# table1.net
KiCad netlist of a schematic drawn in EasyEDA
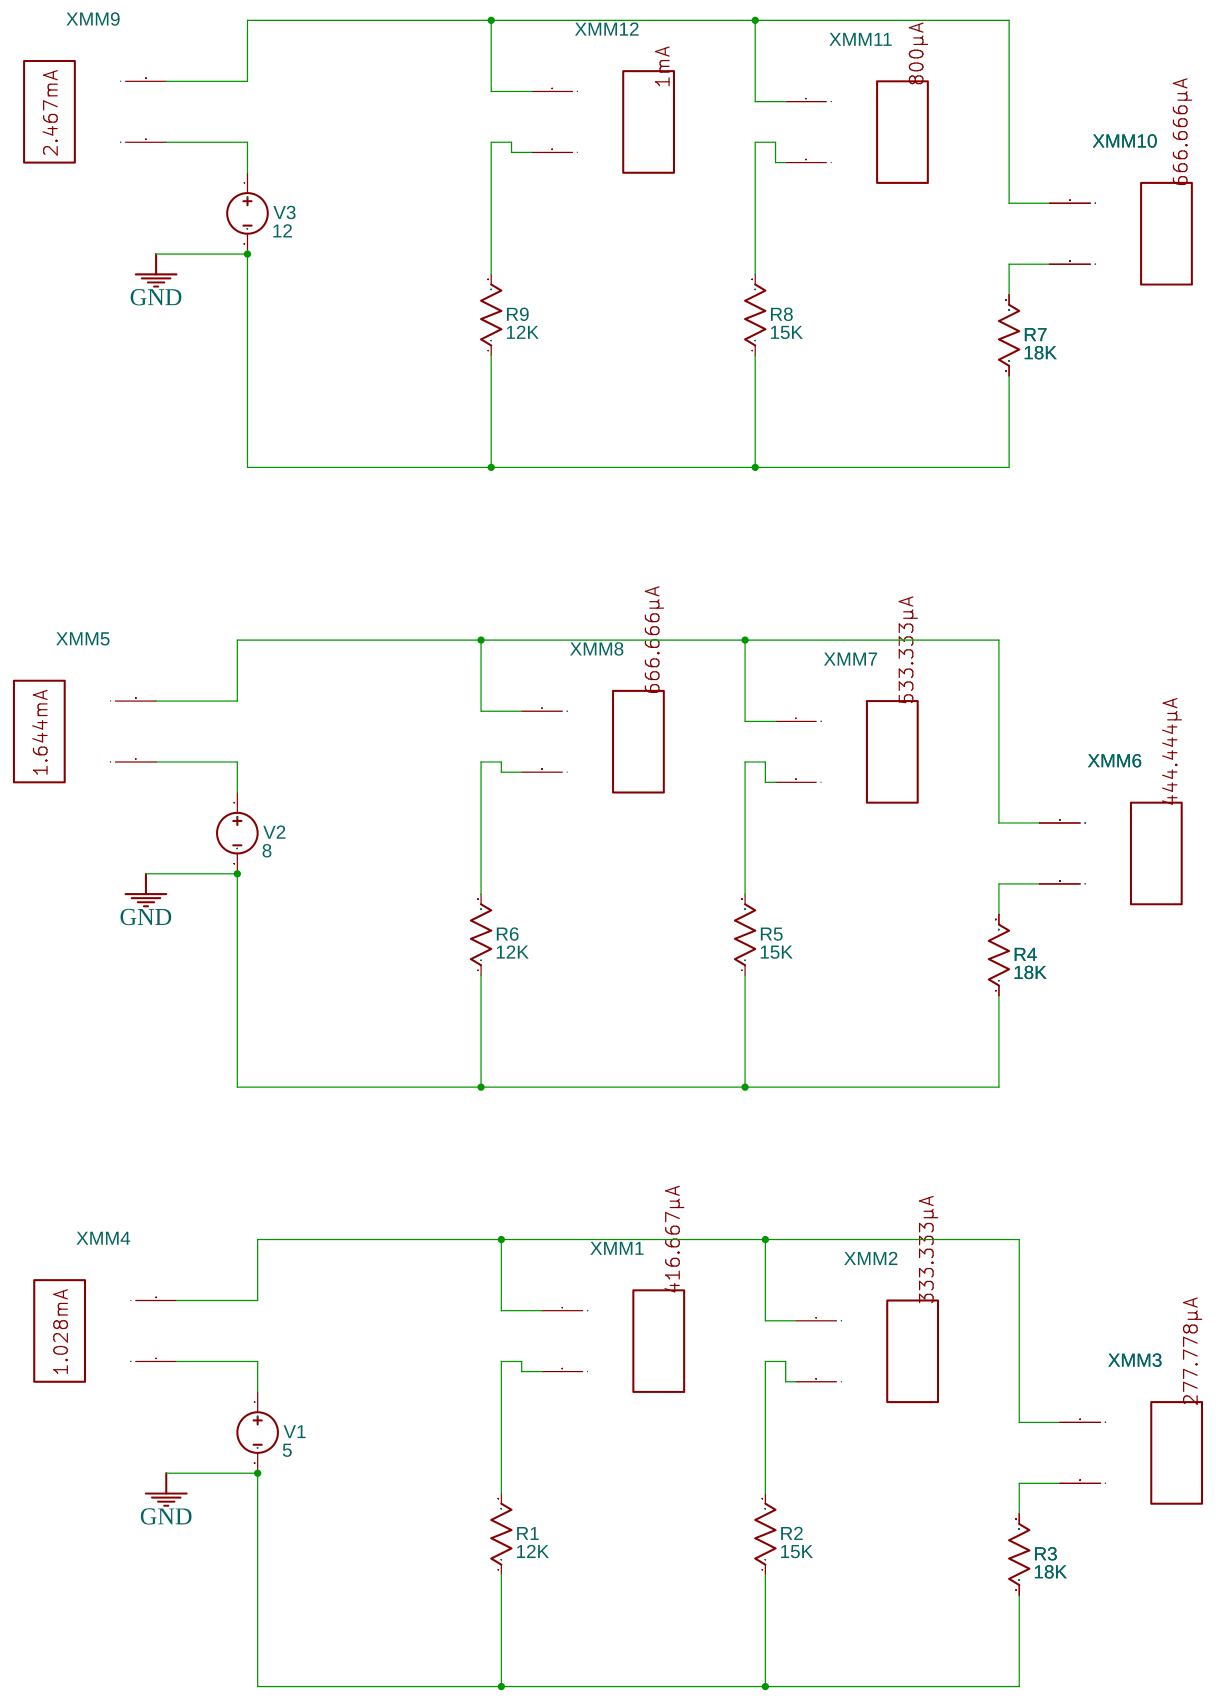
[diagram p0: schematic sheet]

(export (version "E")
  (design (tool "Eeschema 10.0.6"))
  (components
    (comp (ref "R1") (value "12K") (libsource (lib "") (part "Resistor_US")))
    (comp (ref "R2") (value "15K") (libsource (lib "") (part "Resistor_US")))
    (comp (ref "R3") (value "18K") (libsource (lib "") (part "Resistor_US")))
    (comp (ref "R4") (value "18K") (libsource (lib "") (part "Resistor_US")))
    (comp (ref "R5") (value "15K") (libsource (lib "") (part "Resistor_US")))
    (comp (ref "R6") (value "12K") (libsource (lib "") (part "Resistor_US")))
    (comp (ref "R7") (value "18K") (libsource (lib "") (part "Resistor_US")))
    (comp (ref "R8") (value "15K") (libsource (lib "") (part "Resistor_US")))
    (comp (ref "R9") (value "12K") (libsource (lib "") (part "Resistor_US")))
    (comp (ref "V1") (value "5") (libsource (lib "") (part "VDC")))
    (comp (ref "V2") (value "8") (libsource (lib "") (part "VDC")))
    (comp (ref "V3") (value "12") (libsource (lib "") (part "VDC")))
    (comp (ref "XMM1") (value "Multimeter") (libsource (lib "") (part "MULTIMETER_6")))
    (comp (ref "XMM2") (value "Multimeter") (libsource (lib "") (part "MULTIMETER_2")))
    (comp (ref "XMM3") (value "Multimeter") (libsource (lib "") (part "MULTIMETER_7")))
    (comp (ref "XMM4") (value "Multimeter") (libsource (lib "") (part "MULTIMETER_8")))
    (comp (ref "XMM5") (value "Multimeter") (libsource (lib "") (part "MULTIMETER_3")))
    (comp (ref "XMM6") (value "Multimeter") (libsource (lib "") (part "MULTIMETER_4")))
    (comp (ref "XMM7") (value "Multimeter") (libsource (lib "") (part "MULTIMETER_1")))
    (comp (ref "XMM8") (value "Multimeter") (libsource (lib "") (part "MULTIMETER")))
    (comp (ref "XMM9") (value "Multimeter") (libsource (lib "") (part "MULTIMETER_9")))
    (comp (ref "XMM10") (value "Multimeter") (libsource (lib "") (part "MULTIMETER")))
    (comp (ref "XMM11") (value "Multimeter") (libsource (lib "") (part "MULTIMETER_5")))
    (comp (ref "XMM12") (value "Multimeter") (libsource (lib "") (part "MULTIMETER_10")))
  )
  (nets
    (net (code "1") (name "GND") (class "Default")
      (node (ref "R1") (pin "1") (pinfunction "1_1") (pintype "unspecified"))
      (node (ref "R2") (pin "1") (pinfunction "1_1") (pintype "unspecified"))
      (node (ref "R3") (pin "1") (pinfunction "1_1") (pintype "unspecified"))
      (node (ref "R4") (pin "1") (pinfunction "1_1") (pintype "unspecified"))
      (node (ref "R5") (pin "1") (pinfunction "1_1") (pintype "unspecified"))
      (node (ref "R6") (pin "1") (pinfunction "1_1") (pintype "unspecified"))
      (node (ref "R7") (pin "1") (pinfunction "1_1") (pintype "unspecified"))
      (node (ref "R8") (pin "1") (pinfunction "1_1") (pintype "unspecified"))
      (node (ref "R9") (pin "1") (pinfunction "1_1") (pintype "unspecified"))
      (node (ref "V1") (pin "2") (pinfunction "2_2") (pintype "unspecified"))
      (node (ref "V2") (pin "2") (pinfunction "2_2") (pintype "unspecified"))
      (node (ref "V3") (pin "2") (pinfunction "2_2") (pintype "unspecified"))
    )
    (net (code "2") (name "Net-(XMM1-+)") (class "Default")
      (node (ref "XMM1") (pin "1") (pinfunction "+_1") (pintype "unspecified"))
      (node (ref "XMM2") (pin "1") (pinfunction "+_1") (pintype "unspecified"))
      (node (ref "XMM3") (pin "1") (pinfunction "+_1") (pintype "unspecified"))
      (node (ref "XMM4") (pin "2") (pinfunction "I_2") (pintype "unspecified"))
    )
    (net (code "3") (name "Net-(XMM1-I)") (class "Default")
      (node (ref "R1") (pin "2") (pinfunction "2_2") (pintype "unspecified"))
      (node (ref "XMM1") (pin "2") (pinfunction "I_2") (pintype "unspecified"))
    )
    (net (code "4") (name "Net-(XMM2-I)") (class "Default")
      (node (ref "R2") (pin "2") (pinfunction "2_2") (pintype "unspecified"))
      (node (ref "XMM2") (pin "2") (pinfunction "I_2") (pintype "unspecified"))
    )
    (net (code "5") (name "Net-(XMM3-I)") (class "Default")
      (node (ref "R3") (pin "2") (pinfunction "2_2") (pintype "unspecified"))
      (node (ref "XMM3") (pin "2") (pinfunction "I_2") (pintype "unspecified"))
    )
    (net (code "6") (name "Net-(XMM4-+)") (class "Default")
      (node (ref "V1") (pin "1") (pinfunction "1_1") (pintype "unspecified"))
      (node (ref "XMM4") (pin "1") (pinfunction "+_1") (pintype "unspecified"))
    )
    (net (code "7") (name "Net-(XMM5-+)") (class "Default")
      (node (ref "V2") (pin "1") (pinfunction "1_1") (pintype "unspecified"))
      (node (ref "XMM5") (pin "1") (pinfunction "+_1") (pintype "unspecified"))
    )
    (net (code "8") (name "Net-(XMM5-I)") (class "Default")
      (node (ref "XMM5") (pin "2") (pinfunction "I_2") (pintype "unspecified"))
      (node (ref "XMM6") (pin "1") (pinfunction "+_1") (pintype "unspecified"))
      (node (ref "XMM7") (pin "1") (pinfunction "+_1") (pintype "unspecified"))
      (node (ref "XMM8") (pin "1") (pinfunction "+_1") (pintype "unspecified"))
    )
    (net (code "9") (name "Net-(XMM6-I)") (class "Default")
      (node (ref "R4") (pin "2") (pinfunction "2_2") (pintype "unspecified"))
      (node (ref "XMM6") (pin "2") (pinfunction "I_2") (pintype "unspecified"))
    )
    (net (code "10") (name "Net-(XMM7-I)") (class "Default")
      (node (ref "R5") (pin "2") (pinfunction "2_2") (pintype "unspecified"))
      (node (ref "XMM7") (pin "2") (pinfunction "I_2") (pintype "unspecified"))
    )
    (net (code "11") (name "Net-(XMM8-I)") (class "Default")
      (node (ref "R6") (pin "2") (pinfunction "2_2") (pintype "unspecified"))
      (node (ref "XMM8") (pin "2") (pinfunction "I_2") (pintype "unspecified"))
    )
    (net (code "12") (name "Net-(XMM9-+)") (class "Default")
      (node (ref "V3") (pin "1") (pinfunction "1_1") (pintype "unspecified"))
      (node (ref "XMM9") (pin "1") (pinfunction "+_1") (pintype "unspecified"))
    )
    (net (code "13") (name "Net-(XMM10-+)") (class "Default")
      (node (ref "XMM10") (pin "1") (pinfunction "+_1") (pintype "unspecified"))
      (node (ref "XMM11") (pin "1") (pinfunction "+_1") (pintype "unspecified"))
      (node (ref "XMM12") (pin "1") (pinfunction "+_1") (pintype "unspecified"))
      (node (ref "XMM9") (pin "2") (pinfunction "I_2") (pintype "unspecified"))
    )
    (net (code "14") (name "Net-(XMM10-I)") (class "Default")
      (node (ref "R7") (pin "2") (pinfunction "2_2") (pintype "unspecified"))
      (node (ref "XMM10") (pin "2") (pinfunction "I_2") (pintype "unspecified"))
    )
    (net (code "15") (name "Net-(XMM11-I)") (class "Default")
      (node (ref "R8") (pin "2") (pinfunction "2_2") (pintype "unspecified"))
      (node (ref "XMM11") (pin "2") (pinfunction "I_2") (pintype "unspecified"))
    )
    (net (code "16") (name "Net-(XMM12-I)") (class "Default")
      (node (ref "R9") (pin "2") (pinfunction "2_2") (pintype "unspecified"))
      (node (ref "XMM12") (pin "2") (pinfunction "I_2") (pintype "unspecified"))
    )
  )
)
